# WBD_02.net
KiCad netlist of a schematic drawn in EAGLE
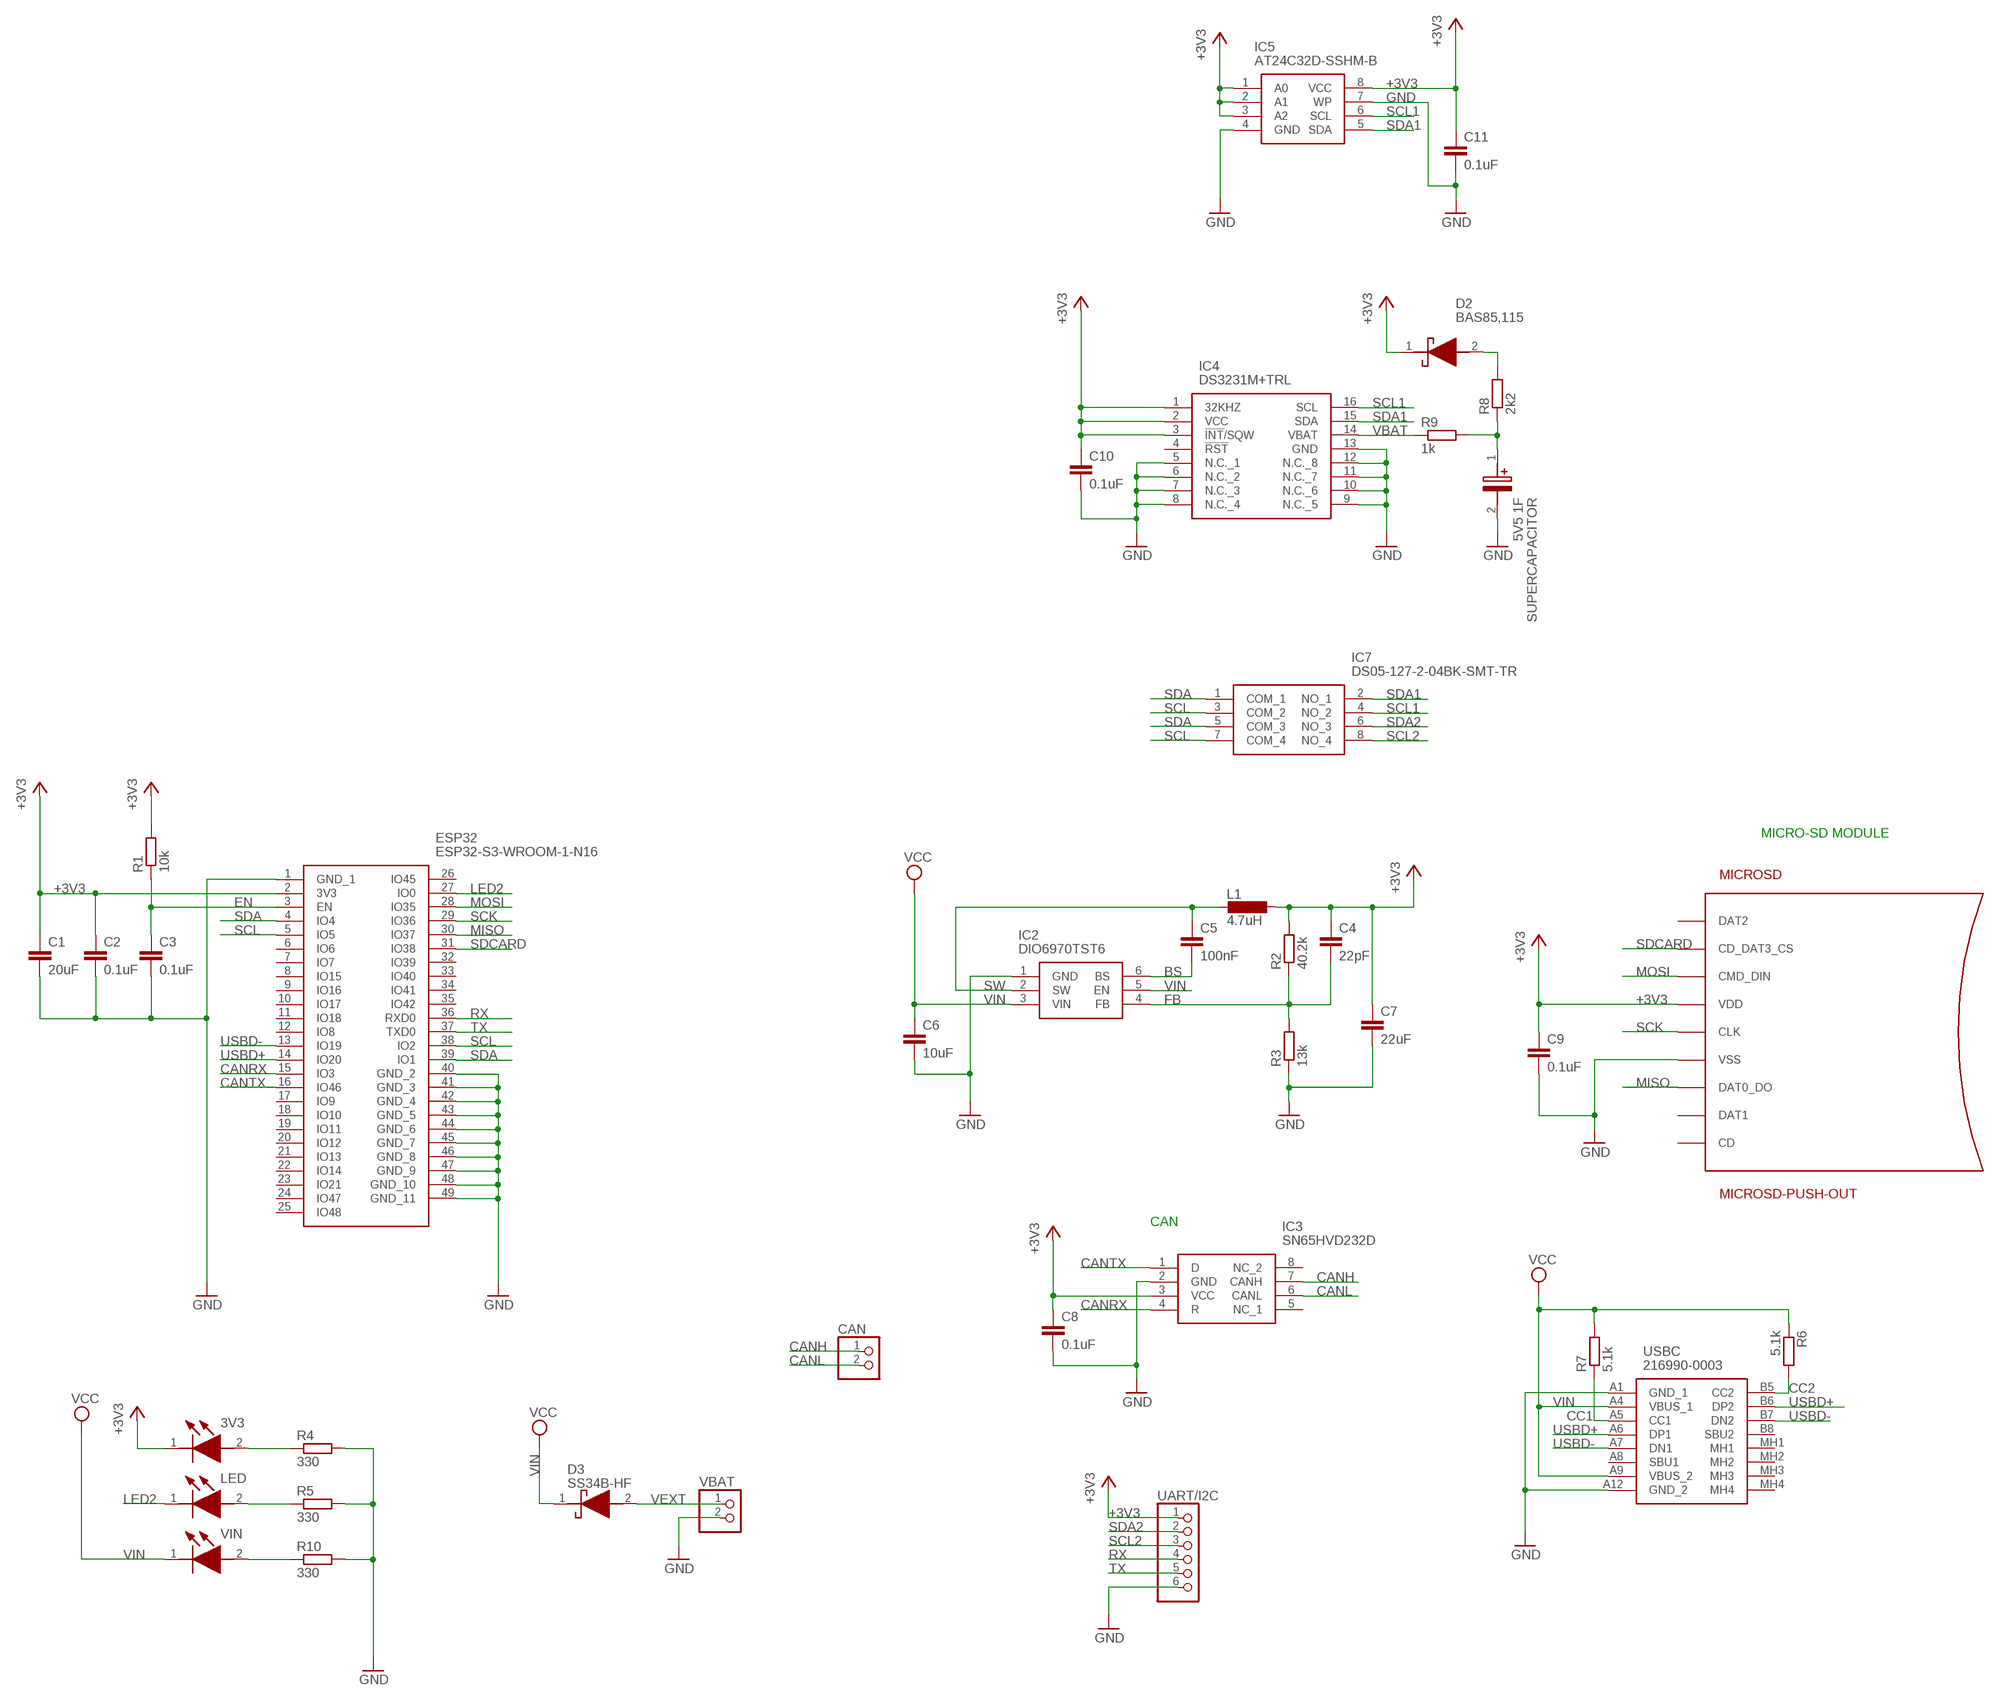
[diagram p0: schematic, sheet 1]

(export (version "E")
  (design (tool "Eeschema 10.0.6"))
  (components
    (comp (ref "3V3")
      (value "150060GS75000")
      (footprint "eagle-import:LEDC1608X80N")
      (fields (field (name "MOUSER_PART_NUMBER") "710-150060GS75000"))
      (libsource (lib "eagle-import") (part "150060GS75000"))
    )
    (comp (ref "C1")
      (value "20uF")
      (footprint "eagle-import:C0603")
      (libsource (lib "eagle-import") (part "C-EUC0603"))
    )
    (comp (ref "C2")
      (value "0.1uF")
      (footprint "eagle-import:C0603")
      (libsource (lib "eagle-import") (part "C-EUC0603"))
    )
    (comp (ref "C3")
      (value "0.1uF")
      (footprint "eagle-import:C0603")
      (libsource (lib "eagle-import") (part "C-EUC0603"))
    )
    (comp (ref "C4")
      (value "22pF")
      (footprint "eagle-import:C0603")
      (libsource (lib "eagle-import") (part "C-EUC0603"))
    )
    (comp (ref "C5")
      (value "100nF")
      (footprint "eagle-import:C0603")
      (libsource (lib "eagle-import") (part "C-EUC0603"))
    )
    (comp (ref "C6")
      (value "10uF")
      (footprint "eagle-import:C0603")
      (libsource (lib "eagle-import") (part "C-EUC0603"))
    )
    (comp (ref "C7")
      (value "22uF")
      (footprint "eagle-import:C0603")
      (libsource (lib "eagle-import") (part "C-EUC0603"))
    )
    (comp (ref "C8")
      (value "0.1uF")
      (footprint "eagle-import:C0603")
      (libsource (lib "eagle-import") (part "C-EUC0603"))
    )
    (comp (ref "C9")
      (value "0.1uF")
      (footprint "eagle-import:C0603")
      (libsource (lib "eagle-import") (part "C-EUC0603"))
    )
    (comp (ref "C10")
      (value "0.1uF")
      (footprint "eagle-import:C0603")
      (libsource (lib "eagle-import") (part "C-EUC0603"))
    )
    (comp (ref "C11")
      (value "0.1uF")
      (footprint "eagle-import:C0603")
      (libsource (lib "eagle-import") (part "C-EUC0603"))
    )
    (comp (ref "CAN")
      (value "PINHD-1X2")
      (footprint "eagle-import:1X02")
      (libsource (lib "eagle-import") (part "PINHD-1X2"))
    )
    (comp (ref "D2")
      (value "BAS85,115")
      (footprint "eagle-import:BAS85115")
      (fields (field (name "MOUSER_PART_NUMBER") "771-BAS85-T/R"))
      (libsource (lib "eagle-import") (part "BAS85,115"))
    )
    (comp (ref "D3")
      (value "SS34B-HF")
      (footprint "eagle-import:DIOM5336X320N")
      (fields (field (name "MOUSER_PART_NUMBER") "750-SS34B-HF"))
      (libsource (lib "eagle-import") (part "SS34B-HF"))
    )
    (comp (ref "ESP32")
      (value "ESP32-S3-WROOM-1-N16")
      (footprint "eagle-import:ESP32S3WROOM1N16")
      (fields (field (name "MOUSER_PART_NUMBER") "356-ESP32S3WROOM1N16"))
      (libsource (lib "eagle-import") (part "ESP32-S3-WROOM-1-N16"))
    )
    (comp (ref "IC2")
      (value "DIO6970TST6")
      (footprint "eagle-import:SOT95P280X90-6N")
      (fields (field (name "MOUSER_PART_NUMBER") "453-DIO6970ST6"))
      (libsource (lib "eagle-import") (part "DIO6970TST6"))
    )
    (comp (ref "IC3")
      (value "SN65HVD232D")
      (footprint "eagle-import:SOIC127P600X175-8N")
      (fields (field (name "MOUSER_PART_NUMBER") "595-SN65HVD232D"))
      (libsource (lib "eagle-import") (part "SN65HVD232D"))
    )
    (comp (ref "IC4")
      (value "DS3231M+TRL")
      (footprint "eagle-import:SOIC127P1032X265-16N")
      (fields (field (name "MOUSER_PART_NUMBER") "700-DS3231M+TRL"))
      (libsource (lib "eagle-import") (part "DS3231M+TRL"))
    )
    (comp (ref "IC5")
      (value "AT24C32D-SSHM-B")
      (footprint "eagle-import:SOIC127P600X175-8N")
      (fields (field (name "MOUSER_PART_NUMBER") "556-AT24C32D-SSHM-B"))
      (libsource (lib "eagle-import") (part "AT24C32D-SSHM-B"))
    )
    (comp (ref "IC7")
      (value "DS05-127-2-04BK-SMT-TR")
      (footprint "eagle-import:DS05127204BKSMTTR")
      (fields (field (name "MOUSER_PART_NUMBER") "490-DS05127204BK-STR"))
      (libsource (lib "eagle-import") (part "DS05-127-2-04BK-SMT-TR"))
    )
    (comp (ref "L1")
      (value "4.7uH")
      (footprint "eagle-import:L5650M")
      (libsource (lib "eagle-import") (part "L-EUL5650M"))
    )
    (comp (ref "LED")
      (value "150060GS75000")
      (footprint "eagle-import:LEDC1608X80N")
      (fields (field (name "MOUSER_PART_NUMBER") "710-150060GS75000"))
      (libsource (lib "eagle-import") (part "150060GS75000"))
    )
    (comp (ref "MICROSD")
      (value "MICROSD-PUSH-OUT")
      (footprint "eagle-import:MICROSD-PUSH-OUT")
      (libsource (lib "eagle-import") (part "MICROSD-PUSH-OUT"))
    )
    (comp (ref "R1")
      (value "10k")
      (footprint "eagle-import:R0603")
      (libsource (lib "eagle-import") (part "R-EU_R0603"))
    )
    (comp (ref "R2")
      (value "40.2k")
      (footprint "eagle-import:R0603")
      (libsource (lib "eagle-import") (part "R-EU_R0603"))
    )
    (comp (ref "R3")
      (value "13k")
      (footprint "eagle-import:R0603")
      (libsource (lib "eagle-import") (part "R-EU_R0603"))
    )
    (comp (ref "R4")
      (value "330")
      (footprint "eagle-import:R0603")
      (libsource (lib "eagle-import") (part "R-EU_R0603"))
    )
    (comp (ref "R5")
      (value "330")
      (footprint "eagle-import:R0603")
      (libsource (lib "eagle-import") (part "R-EU_R0603"))
    )
    (comp (ref "R6")
      (value "5.1k")
      (footprint "eagle-import:R0603")
      (libsource (lib "eagle-import") (part "R-EU_R0603"))
    )
    (comp (ref "R7")
      (value "5.1k")
      (footprint "eagle-import:R0603")
      (libsource (lib "eagle-import") (part "R-EU_R0603"))
    )
    (comp (ref "R8")
      (value "2k2")
      (footprint "eagle-import:R0603")
      (libsource (lib "eagle-import") (part "R-EU_R0603"))
    )
    (comp (ref "R9")
      (value "1k")
      (footprint "eagle-import:R0603")
      (libsource (lib "eagle-import") (part "R-EU_R0603"))
    )
    (comp (ref "R10")
      (value "330")
      (footprint "eagle-import:R0603")
      (libsource (lib "eagle-import") (part "R-EU_R0603"))
    )
    (comp (ref "SUPERCAPACITOR")
      (value "5V5 1F")
      (footprint "eagle-import:CAPPRD500W130D2150H800")
      (fields
        (field (name "MANUFACTURER_PART_NUMBER") "DB-5R5D105T")
        (field (name "MOUSER_PART_NUMBER") "555-DB-5R5D105T")
      )
      (libsource (lib "eagle-import") (part "DB-5R5D105T"))
    )
    (comp (ref "UART/I2C")
      (value "PINHD-1X6")
      (footprint "eagle-import:1X06")
      (libsource (lib "eagle-import") (part "PINHD-1X6"))
    )
    (comp (ref "USBC")
      (value "216990-0003")
      (footprint "eagle-import:2169900003")
      (fields (field (name "MOUSER_PART_NUMBER") "538-216990-0003"))
      (libsource (lib "eagle-import") (part "216990-0003"))
    )
    (comp (ref "VBAT")
      (value "PINHD-1X2")
      (footprint "eagle-import:1X02")
      (libsource (lib "eagle-import") (part "PINHD-1X2"))
    )
    (comp (ref "VIN")
      (value "150060GS75000")
      (footprint "eagle-import:LEDC1608X80N")
      (fields (field (name "MOUSER_PART_NUMBER") "710-150060GS75000"))
      (libsource (lib "eagle-import") (part "150060GS75000"))
    )
  )
  (nets
    (net (code "1") (name "+3V3") (class "Default")
      (node (ref "3V3") (pin "1") (pinfunction "K_1") (pintype "bidirectional"))
      (node (ref "C1") (pin "1") (pinfunction "1_1") (pintype "passive"))
      (node (ref "C10") (pin "1") (pinfunction "1_1") (pintype "passive"))
      (node (ref "C11") (pin "1") (pinfunction "1_1") (pintype "passive"))
      (node (ref "C2") (pin "1") (pinfunction "1_1") (pintype "passive"))
      (node (ref "C4") (pin "1") (pinfunction "1_1") (pintype "passive"))
      (node (ref "C7") (pin "1") (pinfunction "1_1") (pintype "passive"))
      (node (ref "C8") (pin "1") (pinfunction "1_1") (pintype "passive"))
      (node (ref "C9") (pin "1") (pinfunction "1_1") (pintype "passive"))
      (node (ref "D2") (pin "1") (pinfunction "K_1") (pintype "bidirectional"))
      (node (ref "ESP32") (pin "2") (pinfunction "3V3_2") (pintype "bidirectional"))
      (node (ref "IC3") (pin "3") (pinfunction "VCC_3") (pintype "bidirectional"))
      (node (ref "IC4") (pin "1") (pinfunction "32KHZ_1") (pintype "bidirectional"))
      (node (ref "IC4") (pin "2") (pinfunction "VCC_2") (pintype "bidirectional"))
      (node (ref "IC4") (pin "3") (pinfunction "~{INT}/SQW_3") (pintype "bidirectional"))
      (node (ref "IC5") (pin "1") (pinfunction "A0_1") (pintype "bidirectional"))
      (node (ref "IC5") (pin "2") (pinfunction "A1_2") (pintype "bidirectional"))
      (node (ref "IC5") (pin "3") (pinfunction "A2_3") (pintype "bidirectional"))
      (node (ref "IC5") (pin "8") (pinfunction "VCC_8") (pintype "bidirectional"))
      (node (ref "L1") (pin "1") (pinfunction "1_1") (pintype "passive"))
      (node (ref "MICROSD") (pin "4") (pinfunction "VDD_4") (pintype "bidirectional"))
      (node (ref "R1") (pin "2") (pinfunction "2_2") (pintype "passive"))
      (node (ref "R2") (pin "2") (pinfunction "2_2") (pintype "passive"))
      (node (ref "UART/I2C") (pin "1") (pinfunction "1_1") (pintype "passive"))
    )
    (net (code "2") (name "/BS") (class "Default")
      (node (ref "C5") (pin "2") (pinfunction "2_2") (pintype "passive"))
      (node (ref "IC2") (pin "6") (pinfunction "BS_6") (pintype "bidirectional"))
    )
    (net (code "3") (name "/CANH") (class "Default")
      (node (ref "CAN") (pin "1") (pinfunction "1_1") (pintype "passive"))
      (node (ref "IC3") (pin "7") (pinfunction "CANH_7") (pintype "bidirectional"))
    )
    (net (code "4") (name "/CANL") (class "Default")
      (node (ref "CAN") (pin "2") (pinfunction "2_2") (pintype "passive"))
      (node (ref "IC3") (pin "6") (pinfunction "CANL_6") (pintype "bidirectional"))
    )
    (net (code "5") (name "/CANRX") (class "Default")
      (node (ref "ESP32") (pin "15") (pinfunction "IO3_15") (pintype "bidirectional"))
      (node (ref "IC3") (pin "4") (pinfunction "R_4") (pintype "bidirectional"))
    )
    (net (code "6") (name "/CANTX") (class "Default")
      (node (ref "ESP32") (pin "16") (pinfunction "IO46_16") (pintype "bidirectional"))
      (node (ref "IC3") (pin "1") (pinfunction "D_1") (pintype "bidirectional"))
    )
    (net (code "7") (name "/CC1") (class "Default")
      (node (ref "R7") (pin "1") (pinfunction "1_1") (pintype "passive"))
      (node (ref "USBC") (pin "A5") (pinfunction "CC1_A5") (pintype "bidirectional"))
    )
    (net (code "8") (name "/CC2") (class "Default")
      (node (ref "R6") (pin "2") (pinfunction "2_2") (pintype "passive"))
      (node (ref "USBC") (pin "B5") (pinfunction "CC2_B5") (pintype "bidirectional"))
    )
    (net (code "9") (name "/EN") (class "Default")
      (node (ref "C3") (pin "1") (pinfunction "1_1") (pintype "passive"))
      (node (ref "ESP32") (pin "3") (pinfunction "EN_3") (pintype "bidirectional"))
      (node (ref "R1") (pin "1") (pinfunction "1_1") (pintype "passive"))
    )
    (net (code "10") (name "/FB") (class "Default")
      (node (ref "C4") (pin "2") (pinfunction "2_2") (pintype "passive"))
      (node (ref "IC2") (pin "4") (pinfunction "FB_4") (pintype "bidirectional"))
      (node (ref "R2") (pin "1") (pinfunction "1_1") (pintype "passive"))
      (node (ref "R3") (pin "2") (pinfunction "2_2") (pintype "passive"))
    )
    (net (code "11") (name "/LED2") (class "Default")
      (node (ref "ESP32") (pin "27") (pinfunction "IO0_27") (pintype "bidirectional"))
      (node (ref "LED") (pin "1") (pinfunction "K_1") (pintype "bidirectional"))
    )
    (net (code "12") (name "/MISO") (class "Default")
      (node (ref "ESP32") (pin "30") (pinfunction "IO37_30") (pintype "bidirectional"))
      (node (ref "MICROSD") (pin "7") (pinfunction "DAT0_DO_7") (pintype "bidirectional"))
    )
    (net (code "13") (name "/MOSI") (class "Default")
      (node (ref "ESP32") (pin "28") (pinfunction "IO35_28") (pintype "bidirectional"))
      (node (ref "MICROSD") (pin "3") (pinfunction "CMD_DIN_3") (pintype "bidirectional"))
    )
    (net (code "14") (name "/RX") (class "Default")
      (node (ref "ESP32") (pin "36") (pinfunction "RXD0_36") (pintype "bidirectional"))
      (node (ref "UART/I2C") (pin "4") (pinfunction "4_4") (pintype "passive"))
    )
    (net (code "15") (name "/SCK") (class "Default")
      (node (ref "ESP32") (pin "29") (pinfunction "IO36_29") (pintype "bidirectional"))
      (node (ref "MICROSD") (pin "5") (pinfunction "CLK_5") (pintype "bidirectional"))
    )
    (net (code "16") (name "/SCL") (class "Default")
      (node (ref "ESP32") (pin "38") (pinfunction "IO2_38") (pintype "bidirectional"))
      (node (ref "ESP32") (pin "5") (pinfunction "IO5_5") (pintype "bidirectional"))
      (node (ref "IC7") (pin "3") (pinfunction "COM_2_3") (pintype "bidirectional"))
      (node (ref "IC7") (pin "7") (pinfunction "COM_4_7") (pintype "bidirectional"))
    )
    (net (code "17") (name "/SCL1") (class "Default")
      (node (ref "IC4") (pin "16") (pinfunction "SCL_16") (pintype "bidirectional"))
      (node (ref "IC5") (pin "6") (pinfunction "SCL_6") (pintype "bidirectional"))
      (node (ref "IC7") (pin "4") (pinfunction "NO_2_4") (pintype "bidirectional"))
    )
    (net (code "18") (name "/SCL2") (class "Default")
      (node (ref "IC7") (pin "8") (pinfunction "NO_4_8") (pintype "bidirectional"))
      (node (ref "UART/I2C") (pin "3") (pinfunction "3_3") (pintype "passive"))
    )
    (net (code "19") (name "/SDA") (class "Default")
      (node (ref "ESP32") (pin "39") (pinfunction "IO1_39") (pintype "bidirectional"))
      (node (ref "ESP32") (pin "4") (pinfunction "IO4_4") (pintype "bidirectional"))
      (node (ref "IC7") (pin "1") (pinfunction "COM_1_1") (pintype "bidirectional"))
      (node (ref "IC7") (pin "5") (pinfunction "COM_3_5") (pintype "bidirectional"))
    )
    (net (code "20") (name "/SDA1") (class "Default")
      (node (ref "IC4") (pin "15") (pinfunction "SDA_15") (pintype "bidirectional"))
      (node (ref "IC5") (pin "5") (pinfunction "SDA_5") (pintype "bidirectional"))
      (node (ref "IC7") (pin "2") (pinfunction "NO_1_2") (pintype "bidirectional"))
    )
    (net (code "21") (name "/SDA2") (class "Default")
      (node (ref "IC7") (pin "6") (pinfunction "NO_3_6") (pintype "bidirectional"))
      (node (ref "UART/I2C") (pin "2") (pinfunction "2_2") (pintype "passive"))
    )
    (net (code "22") (name "/SDCARD") (class "Default")
      (node (ref "ESP32") (pin "31") (pinfunction "IO38_31") (pintype "bidirectional"))
      (node (ref "MICROSD") (pin "2") (pinfunction "CD_DAT3_CS_2") (pintype "bidirectional"))
    )
    (net (code "23") (name "/SW") (class "Default")
      (node (ref "C5") (pin "1") (pinfunction "1_1") (pintype "passive"))
      (node (ref "IC2") (pin "2") (pinfunction "SW_2") (pintype "bidirectional"))
      (node (ref "L1") (pin "2") (pinfunction "2_2") (pintype "passive"))
    )
    (net (code "24") (name "/TX") (class "Default")
      (node (ref "ESP32") (pin "37") (pinfunction "TXD0_37") (pintype "bidirectional"))
      (node (ref "UART/I2C") (pin "5") (pinfunction "5_5") (pintype "passive"))
    )
    (net (code "25") (name "/USBD+") (class "Default")
      (node (ref "ESP32") (pin "14") (pinfunction "IO20_14") (pintype "bidirectional"))
      (node (ref "USBC") (pin "A6") (pinfunction "DP1_A6") (pintype "bidirectional"))
      (node (ref "USBC") (pin "B6") (pinfunction "DP2_B6") (pintype "bidirectional"))
    )
    (net (code "26") (name "/USBD-") (class "Default")
      (node (ref "ESP32") (pin "13") (pinfunction "IO19_13") (pintype "bidirectional"))
      (node (ref "USBC") (pin "A7") (pinfunction "DN1_A7") (pintype "bidirectional"))
      (node (ref "USBC") (pin "B7") (pinfunction "DN2_B7") (pintype "bidirectional"))
    )
    (net (code "27") (name "/VBAT") (class "Default")
      (node (ref "IC4") (pin "14") (pinfunction "VBAT_14") (pintype "bidirectional"))
      (node (ref "R9") (pin "1") (pinfunction "1_1") (pintype "passive"))
    )
    (net (code "28") (name "/VEXT") (class "Default")
      (node (ref "D3") (pin "2") (pinfunction "A_2") (pintype "bidirectional"))
      (node (ref "VBAT") (pin "1") (pinfunction "1_1") (pintype "passive"))
    )
    (net (code "29") (name "GND") (class "Default")
      (node (ref "C1") (pin "2") (pinfunction "2_2") (pintype "passive"))
      (node (ref "C10") (pin "2") (pinfunction "2_2") (pintype "passive"))
      (node (ref "C11") (pin "2") (pinfunction "2_2") (pintype "passive"))
      (node (ref "C2") (pin "2") (pinfunction "2_2") (pintype "passive"))
      (node (ref "C3") (pin "2") (pinfunction "2_2") (pintype "passive"))
      (node (ref "C6") (pin "2") (pinfunction "2_2") (pintype "passive"))
      (node (ref "C7") (pin "2") (pinfunction "2_2") (pintype "passive"))
      (node (ref "C8") (pin "2") (pinfunction "2_2") (pintype "passive"))
      (node (ref "C9") (pin "2") (pinfunction "2_2") (pintype "passive"))
      (node (ref "ESP32") (pin "1") (pinfunction "GND_1_1") (pintype "bidirectional"))
      (node (ref "ESP32") (pin "40") (pinfunction "GND_2_40") (pintype "bidirectional"))
      (node (ref "ESP32") (pin "41") (pinfunction "GND_3_41") (pintype "bidirectional"))
      (node (ref "ESP32") (pin "42") (pinfunction "GND_4_42") (pintype "bidirectional"))
      (node (ref "ESP32") (pin "43") (pinfunction "GND_5_43") (pintype "bidirectional"))
      (node (ref "ESP32") (pin "44") (pinfunction "GND_6_44") (pintype "bidirectional"))
      (node (ref "ESP32") (pin "45") (pinfunction "GND_7_45") (pintype "bidirectional"))
      (node (ref "ESP32") (pin "46") (pinfunction "GND_8_46") (pintype "bidirectional"))
      (node (ref "ESP32") (pin "47") (pinfunction "GND_9_47") (pintype "bidirectional"))
      (node (ref "ESP32") (pin "48") (pinfunction "GND_10_48") (pintype "bidirectional"))
      (node (ref "ESP32") (pin "49") (pinfunction "GND_11_49") (pintype "bidirectional"))
      (node (ref "IC2") (pin "1") (pinfunction "GND_1") (pintype "bidirectional"))
      (node (ref "IC3") (pin "2") (pinfunction "GND_2") (pintype "bidirectional"))
      (node (ref "IC4") (pin "10") (pinfunction "N.C._6_10") (pintype "bidirectional"))
      (node (ref "IC4") (pin "11") (pinfunction "N.C._7_11") (pintype "bidirectional"))
      (node (ref "IC4") (pin "12") (pinfunction "N.C._8_12") (pintype "bidirectional"))
      (node (ref "IC4") (pin "13") (pinfunction "GND_13") (pintype "bidirectional"))
      (node (ref "IC4") (pin "5") (pinfunction "N.C._1_5") (pintype "bidirectional"))
      (node (ref "IC4") (pin "6") (pinfunction "N.C._2_6") (pintype "bidirectional"))
      (node (ref "IC4") (pin "7") (pinfunction "N.C._3_7") (pintype "bidirectional"))
      (node (ref "IC4") (pin "8") (pinfunction "N.C._4_8") (pintype "bidirectional"))
      (node (ref "IC4") (pin "9") (pinfunction "N.C._5_9") (pintype "bidirectional"))
      (node (ref "IC5") (pin "4") (pinfunction "GND_4") (pintype "bidirectional"))
      (node (ref "IC5") (pin "7") (pinfunction "WP_7") (pintype "bidirectional"))
      (node (ref "MICROSD") (pin "6") (pinfunction "VSS_6") (pintype "bidirectional"))
      (node (ref "MICROSD") (pin "G1") (pinfunction "VSS_G1") (pintype "bidirectional"))
      (node (ref "MICROSD") (pin "G2") (pinfunction "VSS_G2") (pintype "bidirectional"))
      (node (ref "MICROSD") (pin "G3") (pinfunction "VSS_G3") (pintype "bidirectional"))
      (node (ref "MICROSD") (pin "G4") (pinfunction "VSS_G4") (pintype "bidirectional"))
      (node (ref "R10") (pin "2") (pinfunction "2_2") (pintype "passive"))
      (node (ref "R3") (pin "1") (pinfunction "1_1") (pintype "passive"))
      (node (ref "R4") (pin "2") (pinfunction "2_2") (pintype "passive"))
      (node (ref "R5") (pin "2") (pinfunction "2_2") (pintype "passive"))
      (node (ref "SUPERCAPACITOR") (pin "2") (pinfunction "-_2") (pintype "bidirectional"))
      (node (ref "UART/I2C") (pin "6") (pinfunction "6_6") (pintype "passive"))
      (node (ref "USBC") (pin "A1") (pinfunction "GND_1_A1") (pintype "bidirectional"))
      (node (ref "USBC") (pin "A12") (pinfunction "GND_2_A12") (pintype "bidirectional"))
      (node (ref "VBAT") (pin "2") (pinfunction "2_2") (pintype "passive"))
    )
    (net (code "30") (name "Net-(3V3-A)") (class "Default")
      (node (ref "3V3") (pin "2") (pinfunction "A_2") (pintype "bidirectional"))
      (node (ref "R4") (pin "1") (pinfunction "1_1") (pintype "passive"))
    )
    (net (code "31") (name "Net-(D2-A)") (class "Default")
      (node (ref "D2") (pin "2") (pinfunction "A_2") (pintype "bidirectional"))
      (node (ref "R8") (pin "2") (pinfunction "2_2") (pintype "passive"))
    )
    (net (code "32") (name "Net-(LED-A)") (class "Default")
      (node (ref "LED") (pin "2") (pinfunction "A_2") (pintype "bidirectional"))
      (node (ref "R5") (pin "1") (pinfunction "1_1") (pintype "passive"))
    )
    (net (code "33") (name "Net-(SUPERCAPACITOR-+)") (class "Default")
      (node (ref "R8") (pin "1") (pinfunction "1_1") (pintype "passive"))
      (node (ref "R9") (pin "2") (pinfunction "2_2") (pintype "passive"))
      (node (ref "SUPERCAPACITOR") (pin "1") (pinfunction "+_1") (pintype "bidirectional"))
    )
    (net (code "34") (name "Net-(VIN-A)") (class "Default")
      (node (ref "R10") (pin "1") (pinfunction "1_1") (pintype "passive"))
      (node (ref "VIN") (pin "2") (pinfunction "A_2") (pintype "bidirectional"))
    )
    (net (code "35") (name "VCC") (class "Default")
      (node (ref "C6") (pin "1") (pinfunction "1_1") (pintype "passive"))
      (node (ref "D3") (pin "1") (pinfunction "K_1") (pintype "bidirectional"))
      (node (ref "IC2") (pin "3") (pinfunction "VIN_3") (pintype "bidirectional"))
      (node (ref "IC2") (pin "5") (pinfunction "EN_5") (pintype "bidirectional"))
      (node (ref "R6") (pin "1") (pinfunction "1_1") (pintype "passive"))
      (node (ref "R7") (pin "2") (pinfunction "2_2") (pintype "passive"))
      (node (ref "USBC") (pin "A4") (pinfunction "VBUS_1_A4") (pintype "bidirectional"))
      (node (ref "USBC") (pin "A9") (pinfunction "VBUS_2_A9") (pintype "bidirectional"))
      (node (ref "VIN") (pin "1") (pinfunction "K_1") (pintype "bidirectional"))
    )
    (net (code "36") (name "unconnected-(ESP32-IO6-Pad6)") (class "Default")
      (node (ref "ESP32") (pin "6") (pinfunction "IO6_6") (pintype "bidirectional"))
    )
    (net (code "37") (name "unconnected-(ESP32-IO7-Pad7)") (class "Default")
      (node (ref "ESP32") (pin "7") (pinfunction "IO7_7") (pintype "bidirectional"))
    )
    (net (code "38") (name "unconnected-(ESP32-IO8-Pad12)") (class "Default")
      (node (ref "ESP32") (pin "12") (pinfunction "IO8_12") (pintype "bidirectional"))
    )
    (net (code "39") (name "unconnected-(ESP32-IO9-Pad17)") (class "Default")
      (node (ref "ESP32") (pin "17") (pinfunction "IO9_17") (pintype "bidirectional"))
    )
    (net (code "40") (name "unconnected-(ESP32-IO10-Pad18)") (class "Default")
      (node (ref "ESP32") (pin "18") (pinfunction "IO10_18") (pintype "bidirectional"))
    )
    (net (code "41") (name "unconnected-(ESP32-IO11-Pad19)") (class "Default")
      (node (ref "ESP32") (pin "19") (pinfunction "IO11_19") (pintype "bidirectional"))
    )
    (net (code "42") (name "unconnected-(ESP32-IO12-Pad20)") (class "Default")
      (node (ref "ESP32") (pin "20") (pinfunction "IO12_20") (pintype "bidirectional"))
    )
    (net (code "43") (name "unconnected-(ESP32-IO13-Pad21)") (class "Default")
      (node (ref "ESP32") (pin "21") (pinfunction "IO13_21") (pintype "bidirectional"))
    )
    (net (code "44") (name "unconnected-(ESP32-IO14-Pad22)") (class "Default")
      (node (ref "ESP32") (pin "22") (pinfunction "IO14_22") (pintype "bidirectional"))
    )
    (net (code "45") (name "unconnected-(ESP32-IO15-Pad8)") (class "Default")
      (node (ref "ESP32") (pin "8") (pinfunction "IO15_8") (pintype "bidirectional"))
    )
    (net (code "46") (name "unconnected-(ESP32-IO16-Pad9)") (class "Default")
      (node (ref "ESP32") (pin "9") (pinfunction "IO16_9") (pintype "bidirectional"))
    )
    (net (code "47") (name "unconnected-(ESP32-IO17-Pad10)") (class "Default")
      (node (ref "ESP32") (pin "10") (pinfunction "IO17_10") (pintype "bidirectional"))
    )
    (net (code "48") (name "unconnected-(ESP32-IO18-Pad11)") (class "Default")
      (node (ref "ESP32") (pin "11") (pinfunction "IO18_11") (pintype "bidirectional"))
    )
    (net (code "49") (name "unconnected-(ESP32-IO21-Pad23)") (class "Default")
      (node (ref "ESP32") (pin "23") (pinfunction "IO21_23") (pintype "bidirectional"))
    )
    (net (code "50") (name "unconnected-(ESP32-IO39-Pad32)") (class "Default")
      (node (ref "ESP32") (pin "32") (pinfunction "IO39_32") (pintype "bidirectional"))
    )
    (net (code "51") (name "unconnected-(ESP32-IO40-Pad33)") (class "Default")
      (node (ref "ESP32") (pin "33") (pinfunction "IO40_33") (pintype "bidirectional"))
    )
    (net (code "52") (name "unconnected-(ESP32-IO41-Pad34)") (class "Default")
      (node (ref "ESP32") (pin "34") (pinfunction "IO41_34") (pintype "bidirectional"))
    )
    (net (code "53") (name "unconnected-(ESP32-IO42-Pad35)") (class "Default")
      (node (ref "ESP32") (pin "35") (pinfunction "IO42_35") (pintype "bidirectional"))
    )
    (net (code "54") (name "unconnected-(ESP32-IO45-Pad26)") (class "Default")
      (node (ref "ESP32") (pin "26") (pinfunction "IO45_26") (pintype "bidirectional"))
    )
    (net (code "55") (name "unconnected-(ESP32-IO47-Pad24)") (class "Default")
      (node (ref "ESP32") (pin "24") (pinfunction "IO47_24") (pintype "bidirectional"))
    )
    (net (code "56") (name "unconnected-(ESP32-IO48-Pad25)") (class "Default")
      (node (ref "ESP32") (pin "25") (pinfunction "IO48_25") (pintype "bidirectional"))
    )
    (net (code "57") (name "unconnected-(IC3-NC_1-Pad5)") (class "Default")
      (node (ref "IC3") (pin "5") (pinfunction "NC_1_5") (pintype "bidirectional"))
    )
    (net (code "58") (name "unconnected-(IC3-NC_2-Pad8)") (class "Default")
      (node (ref "IC3") (pin "8") (pinfunction "NC_2_8") (pintype "bidirectional"))
    )
    (net (code "59") (name "unconnected-(IC4-~{RST}-Pad4)") (class "Default")
      (node (ref "IC4") (pin "4") (pinfunction "~{RST}_4") (pintype "bidirectional"))
    )
    (net (code "60") (name "unconnected-(MICROSD-DAT1-Pad8)") (class "Default")
      (node (ref "MICROSD") (pin "8") (pinfunction "DAT1_8") (pintype "bidirectional"))
    )
    (net (code "61") (name "unconnected-(MICROSD-DAT2-Pad1)") (class "Default")
      (node (ref "MICROSD") (pin "1") (pinfunction "DAT2_1") (pintype "bidirectional"))
    )
    (net (code "62") (name "unconnected-(MICROSD-PadCD)") (class "Default")
      (node (ref "MICROSD") (pin "CD") (pinfunction "CD_CD") (pintype "bidirectional"))
    )
    (net (code "63") (name "unconnected-(USBC-PadMH1)") (class "Default")
      (node (ref "USBC") (pin "MH1") (pinfunction "MH1_MH1") (pintype "bidirectional"))
    )
    (net (code "64") (name "unconnected-(USBC-PadMH2)") (class "Default")
      (node (ref "USBC") (pin "MH2") (pinfunction "MH2_MH2") (pintype "bidirectional"))
    )
    (net (code "65") (name "unconnected-(USBC-PadMH3)") (class "Default")
      (node (ref "USBC") (pin "MH3") (pinfunction "MH3_MH3") (pintype "bidirectional"))
    )
    (net (code "66") (name "unconnected-(USBC-PadMH4)") (class "Default")
      (node (ref "USBC") (pin "MH4") (pinfunction "MH4_MH4") (pintype "bidirectional"))
    )
    (net (code "67") (name "unconnected-(USBC-SBU1-PadA8)") (class "Default")
      (node (ref "USBC") (pin "A8") (pinfunction "SBU1_A8") (pintype "bidirectional"))
    )
    (net (code "68") (name "unconnected-(USBC-SBU2-PadB8)") (class "Default")
      (node (ref "USBC") (pin "B8") (pinfunction "SBU2_B8") (pintype "bidirectional"))
    )
  )
)
